# Multi-channel_diff-pairs.net
KiCad netlist of a schematic drawn in Altium Designer
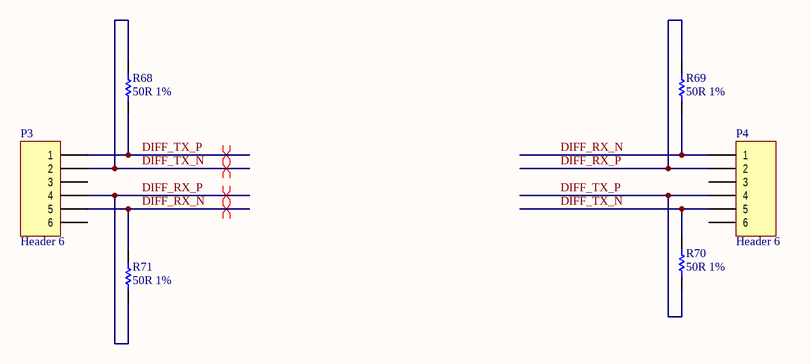
[diagram p0: Multi-channel_diff-pairs.SchDoc]

(export (version "E")
  (design (tool "Eeschema 10.0.6"))
  (components
    (comp (ref "P3")
      (value "Header 6")
      (footprint "HDR1X6")
      (description "Header, 6-Pin")
      (fields (field (name "PUBLISHER") "Altium Limited"))
      (libsource (lib "") (part "Header 6_1"))
    )
    (comp (ref "P4")
      (value "Header 6")
      (footprint "HDR1X6")
      (description "Header, 6-Pin")
      (fields (field (name "PUBLISHER") "Altium Limited"))
      (libsource (lib "Miscellaneous Connectors") (part "Header 6"))
    )
    (comp (ref "R68")
      (value "50R 1%")
      (footprint "RESC2012")
      (description "Resistor")
      (libsource (lib "NBP-28") (part "RES"))
    )
    (comp (ref "R69")
      (value "50R 1%")
      (footprint "RESC2012")
      (description "Resistor")
      (libsource (lib "NBP-28") (part "RES"))
    )
    (comp (ref "R70")
      (value "50R 1%")
      (footprint "RESC2012")
      (description "Resistor")
      (libsource (lib "NBP-28") (part "RES"))
    )
    (comp (ref "R71")
      (value "50R 1%")
      (footprint "RESC2012")
      (description "Resistor")
      (libsource (lib "NBP-28") (part "RES"))
    )
  )
  (nets
    (net (code "1") (name "/DIFF_RX_N") (class "Default")
      (node (ref "P3") (pin "5") (pinfunction "5_5") (pintype "passive"))
      (node (ref "P4") (pin "1") (pinfunction "1_1") (pintype "passive"))
      (node (ref "R69") (pin "2") (pinfunction "2_2") (pintype "passive"))
      (node (ref "R71") (pin "1") (pinfunction "1_1") (pintype "passive"))
    )
    (net (code "2") (name "/DIFF_RX_P") (class "Default")
      (node (ref "P3") (pin "4") (pinfunction "4_4") (pintype "passive"))
      (node (ref "P4") (pin "2") (pinfunction "2_2") (pintype "passive"))
      (node (ref "R69") (pin "1") (pinfunction "1_1") (pintype "passive"))
      (node (ref "R71") (pin "2") (pinfunction "2_2") (pintype "passive"))
    )
    (net (code "3") (name "/DIFF_TX_N") (class "Default")
      (node (ref "P3") (pin "2") (pinfunction "2_2") (pintype "passive"))
      (node (ref "P4") (pin "5") (pinfunction "5_5") (pintype "passive"))
      (node (ref "R68") (pin "1") (pinfunction "1_1") (pintype "passive"))
      (node (ref "R70") (pin "1") (pinfunction "1_1") (pintype "passive"))
    )
    (net (code "4") (name "/DIFF_TX_P") (class "Default")
      (node (ref "P3") (pin "1") (pinfunction "1_1") (pintype "passive"))
      (node (ref "P4") (pin "4") (pinfunction "4_4") (pintype "passive"))
      (node (ref "R68") (pin "2") (pinfunction "2_2") (pintype "passive"))
      (node (ref "R70") (pin "2") (pinfunction "2_2") (pintype "passive"))
    )
    (net (code "5") (name "unconnected-(P3-Pad3)") (class "Default")
      (node (ref "P3") (pin "3") (pinfunction "3_3") (pintype "passive"))
    )
    (net (code "6") (name "unconnected-(P3-Pad6)") (class "Default")
      (node (ref "P3") (pin "6") (pinfunction "6_6") (pintype "passive"))
    )
    (net (code "7") (name "unconnected-(P4-Pad3)") (class "Default")
      (node (ref "P4") (pin "3") (pinfunction "3_3") (pintype "passive"))
    )
    (net (code "8") (name "unconnected-(P4-Pad6)") (class "Default")
      (node (ref "P4") (pin "6") (pinfunction "6_6") (pintype "passive"))
    )
  )
)
